# scribe.net
KiCad netlist of a schematic drawn in EasyEDA Pro
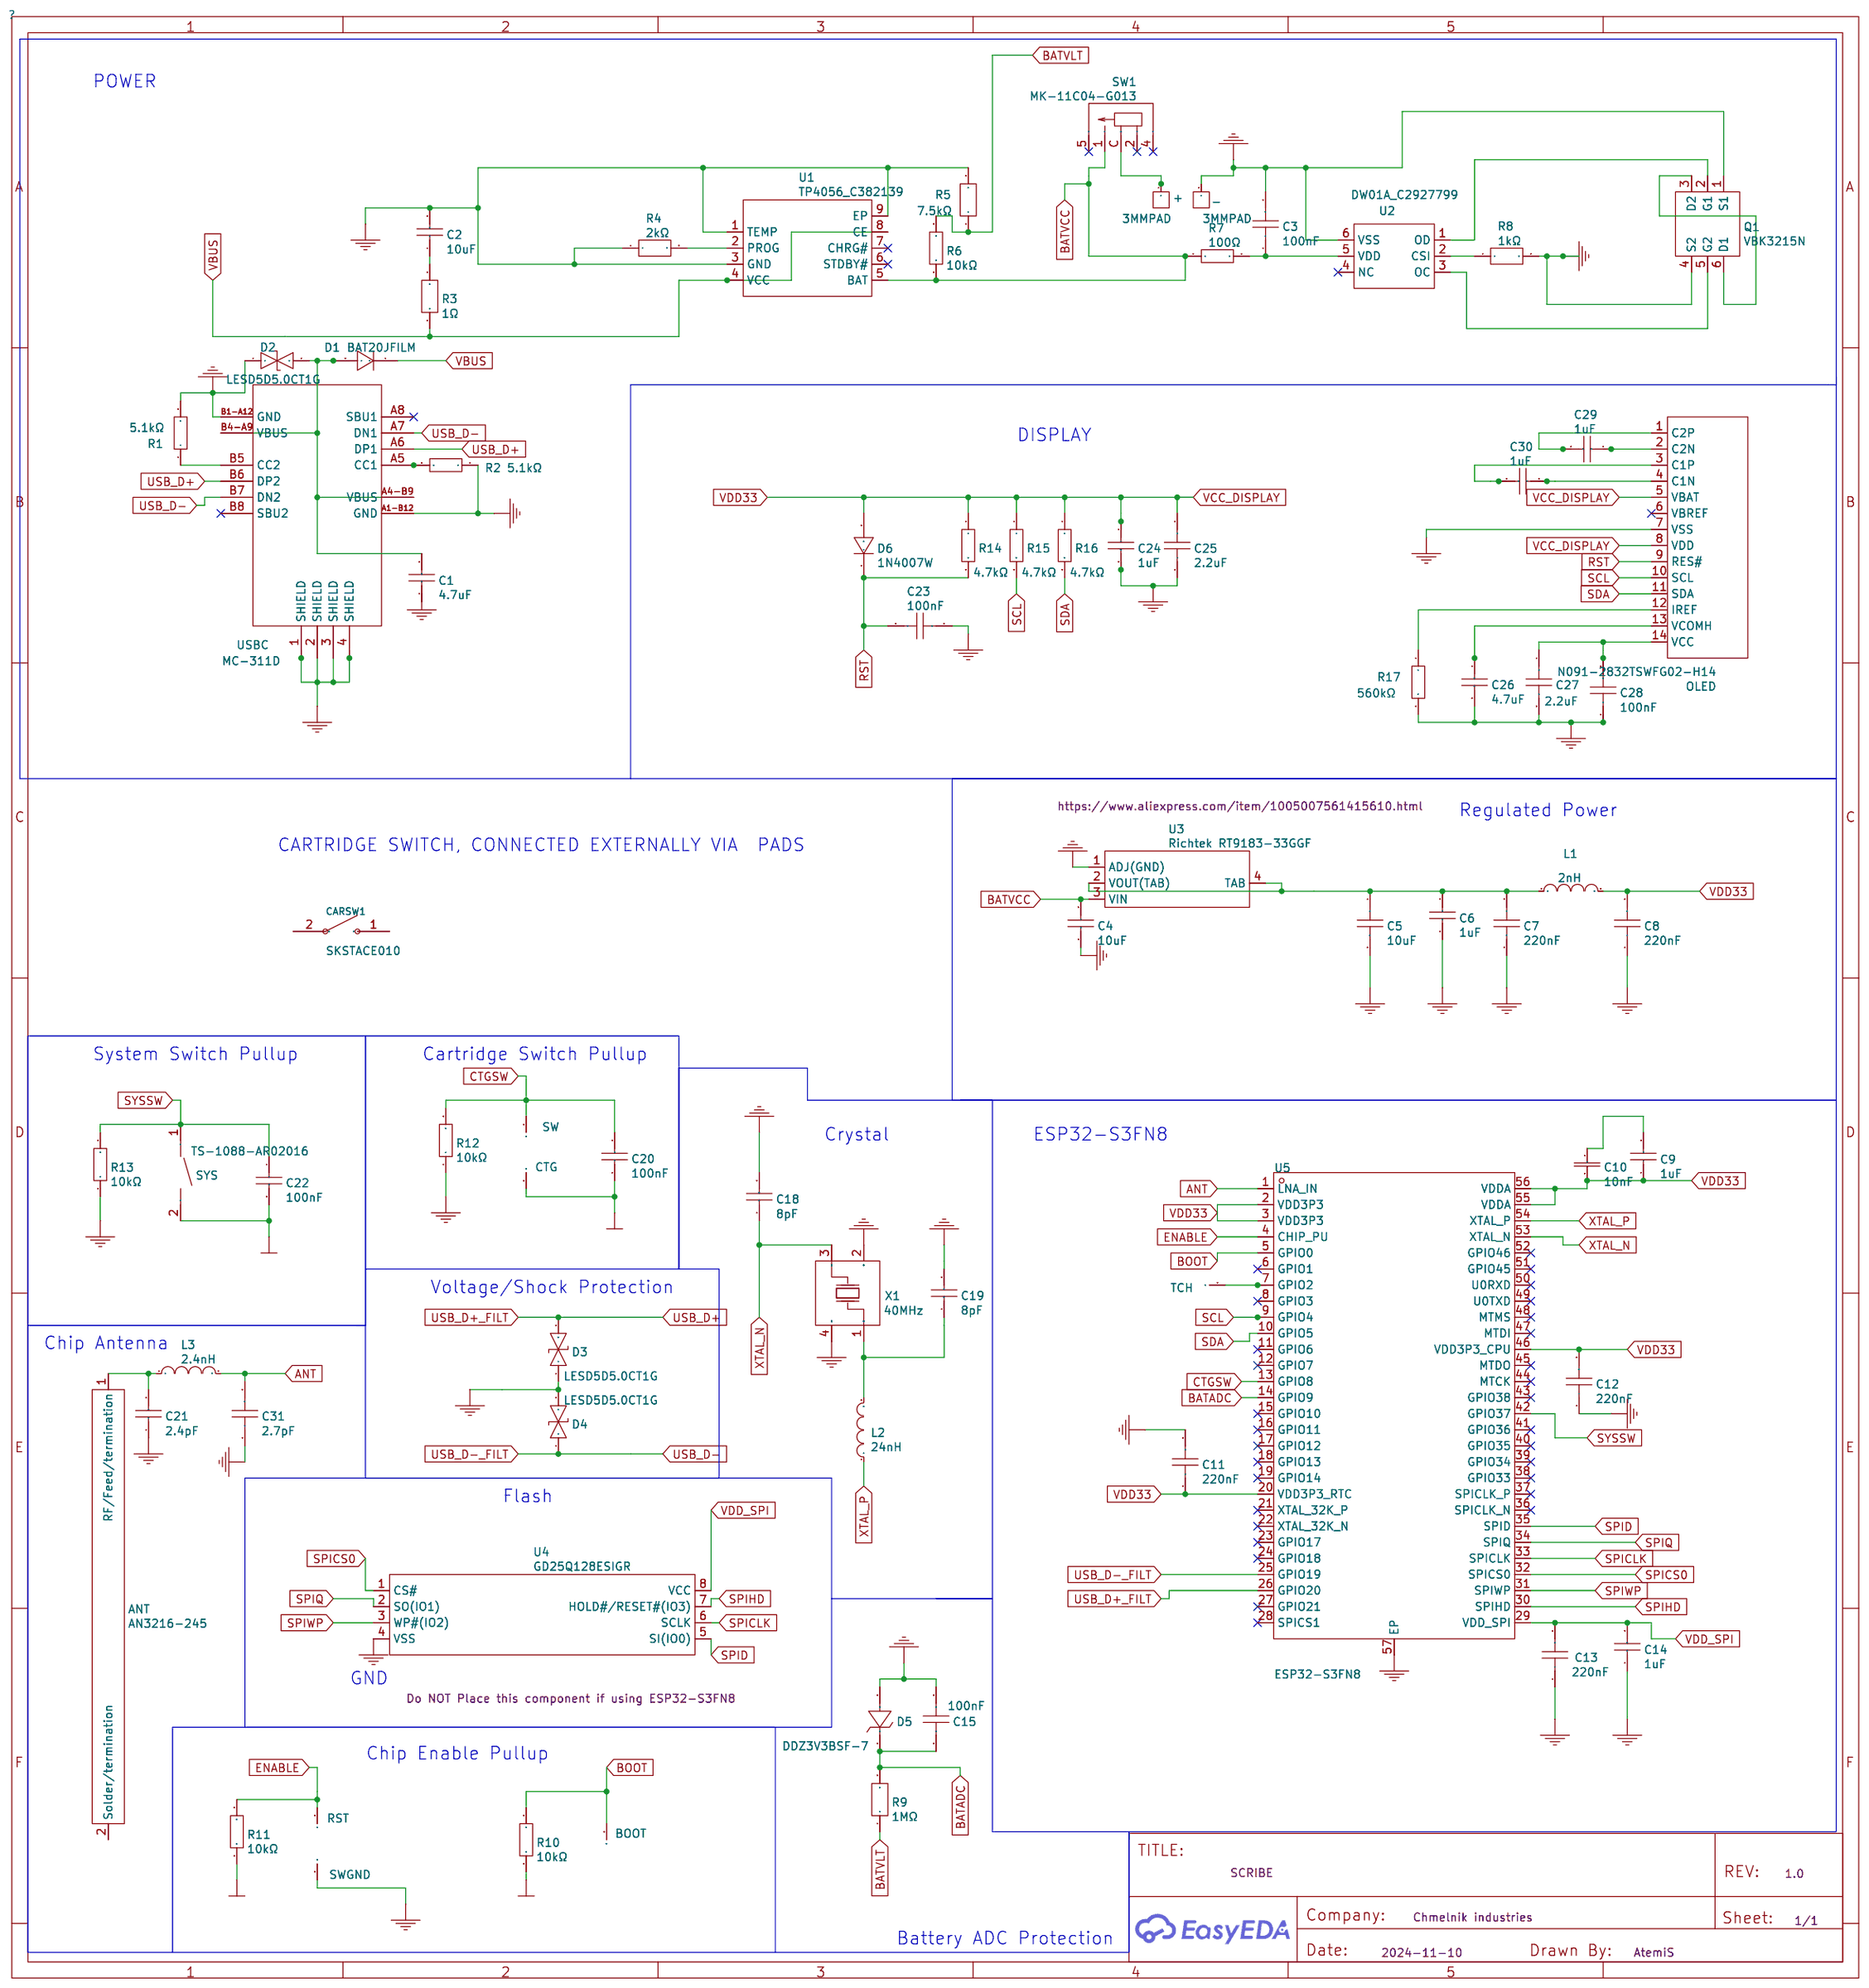
[diagram p0: schematic sheet]

(export (version "E")
  (design (tool "Eeschema 10.0.6"))
  (components
    (comp (ref "+")
      (value "3MMPAD")
      (footprint "easyedapro:3MMPAD")
      (libsource (lib "easyedapro") (part "3MMPAD"))
    )
    (comp (ref "ANT")
      (value "AN3216-245")
      (footprint "easyedapro:ANT-SMD_L3.2-W1.6-A")
      (fields (field (name "Manufacturer") "rainsun(霖昱微)"))
      (libsource (lib "easyedapro") (part "AN3216-245"))
    )
    (comp (ref "BOOT")
      (value "PAD_TERMINAL-32MIL_ROUND")
      (footprint "easyedapro:CON_PAD_ROUND_32MIL")
      (libsource (lib "easyedapro") (part "PAD_TERMINAL-32MIL_ROUND"))
    )
    (comp (ref "C1")
      (value "4.7uF")
      (footprint "easyedapro:C0805")
      (fields
        (field (name "Manufacturer Part") "CL21A475KAQNNNE")
        (field (name "Manufacturer") "SAMSUNG(三星)")
      )
      (libsource (lib "easyedapro") (part "4.7uF"))
    )
    (comp (ref "C2")
      (value "10uF")
      (footprint "easyedapro:C0402")
      (fields
        (field (name "Manufacturer Part") "CL05A106MQ5NUNC")
        (field (name "Manufacturer") "SAMSUNG(三星)")
      )
      (libsource (lib "easyedapro") (part "10uF"))
    )
    (comp (ref "C3")
      (value "100nF")
      (footprint "easyedapro:C0603")
      (fields
        (field (name "Manufacturer Part") "CC0603KRX7R9BB104")
        (field (name "Manufacturer") "YAGEO(国巨)")
      )
      (libsource (lib "easyedapro") (part "100nF"))
    )
    (comp (ref "C4")
      (value "10uF")
      (footprint "easyedapro:C0402")
      (fields
        (field (name "Manufacturer Part") "CL05A106MQ5NUNC")
        (field (name "Manufacturer") "SAMSUNG(三星)")
      )
      (libsource (lib "easyedapro") (part "10uF"))
    )
    (comp (ref "C5")
      (value "10uF")
      (footprint "easyedapro:C0603")
      (fields
        (field (name "Manufacturer Part") "CL10A106KP8NNNC")
        (field (name "Manufacturer") "SAMSUNG(三星)")
      )
      (libsource (lib "") (part "10uF_1"))
    )
    (comp (ref "C6")
      (value "1uF")
      (footprint "easyedapro:C0402")
      (fields
        (field (name "Manufacturer Part") "GRM155R61C105KA12D")
        (field (name "Manufacturer") "muRata(村田)")
      )
      (libsource (lib "easyedapro") (part "1uF"))
    )
    (comp (ref "C7")
      (value "220nF")
      (footprint "easyedapro:C0402")
      (fields
        (field (name "Manufacturer Part") "C0402X7R224K160NT")
        (field (name "Manufacturer") "SANYEAR(叁叶源)")
      )
      (libsource (lib "easyedapro") (part "220nF"))
    )
    (comp (ref "C8")
      (value "220nF")
      (footprint "easyedapro:C0402")
      (fields
        (field (name "Manufacturer Part") "C0402X7R224K160NT")
        (field (name "Manufacturer") "SANYEAR(叁叶源)")
      )
      (libsource (lib "easyedapro") (part "220nF"))
    )
    (comp (ref "C9")
      (value "1uF")
      (footprint "easyedapro:C0402")
      (fields
        (field (name "Manufacturer Part") "GRM155R61C105KA12D")
        (field (name "Manufacturer") "muRata(村田)")
      )
      (libsource (lib "easyedapro") (part "1uF"))
    )
    (comp (ref "C10")
      (value "10nF")
      (footprint "easyedapro:C0201")
      (fields (field (name "Manufacturer Part") "C0603X5R103KDT") (field (name "Manufacturer") "DARFON(达方)"))
      (libsource (lib "easyedapro") (part "10nF"))
    )
    (comp (ref "C11")
      (value "220nF")
      (footprint "easyedapro:C0402")
      (fields
        (field (name "Manufacturer Part") "C0402X7R224K160NT")
        (field (name "Manufacturer") "SANYEAR(叁叶源)")
      )
      (libsource (lib "easyedapro") (part "220nF"))
    )
    (comp (ref "C12")
      (value "220nF")
      (footprint "easyedapro:C0402")
      (fields
        (field (name "Manufacturer Part") "C0402X7R224K160NT")
        (field (name "Manufacturer") "SANYEAR(叁叶源)")
      )
      (libsource (lib "easyedapro") (part "220nF"))
    )
    (comp (ref "C13")
      (value "220nF")
      (footprint "easyedapro:C0402")
      (fields
        (field (name "Manufacturer Part") "C0402X7R224K160NT")
        (field (name "Manufacturer") "SANYEAR(叁叶源)")
      )
      (libsource (lib "easyedapro") (part "220nF"))
    )
    (comp (ref "C14")
      (value "1uF")
      (footprint "easyedapro:C0402")
      (fields
        (field (name "Manufacturer Part") "GRM155R61C105KA12D")
        (field (name "Manufacturer") "muRata(村田)")
      )
      (libsource (lib "easyedapro") (part "1uF"))
    )
    (comp (ref "C15")
      (value "100nF")
      (footprint "easyedapro:C0603")
      (fields
        (field (name "Manufacturer Part") "CC0603KRX7R9BB104")
        (field (name "Manufacturer") "YAGEO(国巨)")
      )
      (libsource (lib "easyedapro") (part "100nF"))
    )
    (comp (ref "C18")
      (value "8pF")
      (footprint "easyedapro:C0402")
      (fields (field (name "Manufacturer Part") "0402CG8R0C500NT") (field (name "Manufacturer") "FH(风华)"))
      (libsource (lib "easyedapro") (part "8pF"))
    )
    (comp (ref "C19")
      (value "8pF")
      (footprint "easyedapro:C0402")
      (fields (field (name "Manufacturer Part") "0402CG8R0C500NT") (field (name "Manufacturer") "FH(风华)"))
      (libsource (lib "easyedapro") (part "8pF"))
    )
    (comp (ref "C20")
      (value "100nF")
      (footprint "easyedapro:C0402")
      (fields
        (field (name "Manufacturer Part") "CL05B104KO5NNNC")
        (field (name "Manufacturer") "SAMSUNG(三星)")
      )
      (libsource (lib "") (part "100nF_1"))
    )
    (comp (ref "C21")
      (value "2.4pF")
      (footprint "easyedapro:C0402")
      (fields (field (name "Manufacturer Part") "0402CG2R4C500NT") (field (name "Manufacturer") "FH(风华)"))
      (libsource (lib "easyedapro") (part "2.4pF"))
    )
    (comp (ref "C22")
      (value "100nF")
      (footprint "easyedapro:C0402")
      (fields
        (field (name "Manufacturer Part") "CL05B104KO5NNNC")
        (field (name "Manufacturer") "SAMSUNG(三星)")
      )
      (libsource (lib "") (part "100nF_1"))
    )
    (comp (ref "C23")
      (value "100nF")
      (footprint "easyedapro:C0603")
      (fields
        (field (name "Manufacturer Part") "CC0603KRX7R9BB104")
        (field (name "Manufacturer") "YAGEO(国巨)")
      )
      (libsource (lib "easyedapro") (part "100nF"))
    )
    (comp (ref "C24")
      (value "1uF")
      (footprint "easyedapro:C0402")
      (fields
        (field (name "Manufacturer Part") "GRM155R61C105KA12D")
        (field (name "Manufacturer") "muRata(村田)")
      )
      (libsource (lib "easyedapro") (part "1uF"))
    )
    (comp (ref "C25")
      (value "2.2uF")
      (footprint "easyedapro:C0603")
      (fields
        (field (name "Manufacturer Part") "C0603C225K8RAC7867")
        (field (name "Manufacturer") "KEMET(基美)")
      )
      (libsource (lib "easyedapro") (part "2.2uF"))
    )
    (comp (ref "C26")
      (value "4.7uF")
      (footprint "easyedapro:C0805")
      (fields
        (field (name "Manufacturer Part") "CL21A475KAQNNNE")
        (field (name "Manufacturer") "SAMSUNG(三星)")
      )
      (libsource (lib "easyedapro") (part "4.7uF"))
    )
    (comp (ref "C27")
      (value "2.2uF")
      (footprint "easyedapro:C0603")
      (fields
        (field (name "Manufacturer Part") "C0603C225K8RAC7867")
        (field (name "Manufacturer") "KEMET(基美)")
      )
      (libsource (lib "easyedapro") (part "2.2uF"))
    )
    (comp (ref "C28")
      (value "100nF")
      (footprint "easyedapro:C0603")
      (fields
        (field (name "Manufacturer Part") "CC0603KRX7R9BB104")
        (field (name "Manufacturer") "YAGEO(国巨)")
      )
      (libsource (lib "easyedapro") (part "100nF"))
    )
    (comp (ref "C29")
      (value "1uF")
      (footprint "easyedapro:C0402")
      (fields
        (field (name "Manufacturer Part") "GRM155R61C105KA12D")
        (field (name "Manufacturer") "muRata(村田)")
      )
      (libsource (lib "easyedapro") (part "1uF"))
    )
    (comp (ref "C30")
      (value "1uF")
      (footprint "easyedapro:C0402")
      (fields
        (field (name "Manufacturer Part") "GRM155R61C105KA12D")
        (field (name "Manufacturer") "muRata(村田)")
      )
      (libsource (lib "easyedapro") (part "1uF"))
    )
    (comp (ref "C31")
      (value "2.7pF")
      (footprint "easyedapro:C0402")
      (fields
        (field (name "Manufacturer Part") "CC0402BRNPO9BN2R7")
        (field (name "Manufacturer") "YAGEO(国巨)")
      )
      (libsource (lib "easyedapro") (part "2.7pF"))
    )
    (comp (ref "CARSW1")
      (value "SKSTACE010")
      (footprint "easyedapro:SW-SMD_L8.5-W8.5-LS8.6")
      (fields (field (name "Manufacturer") "ALPSALPINE(阿尔卑斯阿尔派)"))
      (libsource (lib "easyedapro") (part "SKSTACE010"))
    )
    (comp (ref "CTG")
      (value "PAD_TERMINAL-32MIL_ROUND")
      (footprint "easyedapro:CON_PAD_ROUND_32MIL")
      (libsource (lib "easyedapro") (part "PAD_TERMINAL-32MIL_ROUND"))
    )
    (comp (ref "D1")
      (value "BAT20JFILM")
      (footprint "easyedapro:SOD-323_L1.8-W1.3-LS2.5-RD")
      (fields (field (name "Manufacturer") "ST(意法半导体)"))
      (libsource (lib "easyedapro") (part "BAT20JFILM"))
    )
    (comp (ref "D2")
      (value "LESD5D5.0CT1G")
      (footprint "easyedapro:SOD-523_L1.2-W0.8-LS1.6-BI")
      (fields (field (name "Manufacturer") "LRC(乐山无线电)"))
      (libsource (lib "easyedapro") (part "LESD5D5.0CT1G"))
    )
    (comp (ref "D3")
      (value "LESD5D5.0CT1G")
      (footprint "easyedapro:SOD-523_L1.2-W0.8-LS1.6-BI")
      (fields (field (name "Manufacturer") "LRC(乐山无线电)"))
      (libsource (lib "easyedapro") (part "LESD5D5.0CT1G"))
    )
    (comp (ref "D4")
      (value "LESD5D5.0CT1G")
      (footprint "easyedapro:SOD-523_L1.2-W0.8-LS1.6-BI")
      (fields (field (name "Manufacturer") "LRC(乐山无线电)"))
      (libsource (lib "easyedapro") (part "LESD5D5.0CT1G"))
    )
    (comp (ref "D5")
      (value "DDZ3V3BSF-7")
      (footprint "easyedapro:SOD-323F_L1.7-W1.3-LS2.5-RD")
      (fields (field (name "Manufacturer") "DIODES(美台)"))
      (libsource (lib "easyedapro") (part "DDZ3V3BSF-7"))
    )
    (comp (ref "D6")
      (value "1N4007W")
      (footprint "easyedapro:SOD-123_L2.8-W1.8-LS3.7-RD")
      (fields (field (name "Manufacturer") "BLUE ROCKET"))
      (libsource (lib "easyedapro") (part "1N4007W"))
    )
    (comp (ref "L1")
      (value "2nH")
      (footprint "easyedapro:L0402-RD")
      (fields (field (name "Manufacturer Part") "MLG1005S2N0BTD25") (field (name "Manufacturer") "TDK"))
      (libsource (lib "easyedapro") (part "2nH"))
    )
    (comp (ref "L2")
      (value "24nH")
      (footprint "easyedapro:IND-SMD_L1.2-W0.6")
      (fields
        (field (name "Manufacturer Part") "SDWL1005C24NJSTF")
        (field (name "Manufacturer") "Sunlord(顺络)")
      )
      (libsource (lib "easyedapro") (part "24nH"))
    )
    (comp (ref "L3")
      (value "2.4nH")
      (footprint "easyedapro:L0402")
      (fields (field (name "Manufacturer Part") "LQG15HS2N4S02D") (field (name "Manufacturer") "muRata(村田)"))
      (libsource (lib "easyedapro") (part "2.4nH"))
    )
    (comp (ref "OLED")
      (value "N091-2832TSWFG02-H14")
      (footprint "easyedapro:OLED-SMD_N091-2832TSWFG02-H14")
      (fields (field (name "Manufacturer") "Newvision(新智景)"))
      (libsource (lib "easyedapro") (part "N091-2832TSWFG02-H14"))
    )
    (comp (ref "Q1")
      (value "VBK3215N")
      (footprint "easyedapro:SC-70-6_L2.2-W1.3-P0.65-LS2.1-BR")
      (fields (field (name "Manufacturer") "VBsemi(微碧半导体)"))
      (libsource (lib "easyedapro") (part "VBK3215N"))
    )
    (comp (ref "R1")
      (value "5.1kΩ")
      (footprint "easyedapro:R0603")
      (fields
        (field (name "Manufacturer Part") "0603WAF5101T5E")
        (field (name "Manufacturer") "UNI-ROYAL(厚声)")
      )
      (libsource (lib "easyedapro") (part "5.1kΩ"))
    )
    (comp (ref "R2")
      (value "5.1kΩ")
      (footprint "easyedapro:R0603")
      (fields
        (field (name "Manufacturer Part") "0603WAF5101T5E")
        (field (name "Manufacturer") "UNI-ROYAL(厚声)")
      )
      (libsource (lib "easyedapro") (part "5.1kΩ"))
    )
    (comp (ref "R3")
      (value "1Ω")
      (footprint "easyedapro:R1206")
      (fields (field (name "Manufacturer Part") "RT1206BRD071RL") (field (name "Manufacturer") "YAGEO(国巨)"))
      (libsource (lib "easyedapro") (part "1Ω"))
    )
    (comp (ref "R4")
      (value "2kΩ")
      (footprint "easyedapro:RES-SMD_L3.5-W1.5")
      (fields
        (field (name "Manufacturer Part") "RJM74P0204F2T2001")
        (field (name "Manufacturer") "Tyohm(幸亚电阻)")
      )
      (libsource (lib "easyedapro") (part "2kΩ"))
    )
    (comp (ref "R5")
      (value "7.5kΩ")
      (footprint "easyedapro:R1206")
      (fields (field (name "Manufacturer Part") "RT1206BRD077K5L") (field (name "Manufacturer") "YAGEO(国巨)"))
      (libsource (lib "easyedapro") (part "7.5kΩ"))
    )
    (comp (ref "R6")
      (value "10kΩ")
      (footprint "easyedapro:R1206")
      (fields (field (name "Manufacturer Part") "RT1206BRD0710KL") (field (name "Manufacturer") "YAGEO(国巨)"))
      (libsource (lib "") (part "10kΩ_1"))
    )
    (comp (ref "R7")
      (value "100Ω")
      (footprint "easyedapro:R1206")
      (fields (field (name "Manufacturer Part") "RT1206BRD07100RL") (field (name "Manufacturer") "YAGEO(国巨)"))
      (libsource (lib "easyedapro") (part "100Ω"))
    )
    (comp (ref "R8")
      (value "1kΩ")
      (footprint "easyedapro:R1206")
      (fields (field (name "Manufacturer Part") "RT1206BRD071KL") (field (name "Manufacturer") "YAGEO(国巨)"))
      (libsource (lib "easyedapro") (part "1kΩ"))
    )
    (comp (ref "R9")
      (value "1MΩ")
      (footprint "easyedapro:R0603")
      (fields (field (name "Manufacturer Part") "ERJP03J105V") (field (name "Manufacturer") "PANASONIC(松下)"))
      (libsource (lib "easyedapro") (part "1MΩ"))
    )
    (comp (ref "R10")
      (value "10kΩ")
      (footprint "easyedapro:R0603")
      (fields
        (field (name "Manufacturer Part") "0603WAF1002T5E")
        (field (name "Manufacturer") "UNI-ROYAL(厚声)")
      )
      (libsource (lib "easyedapro") (part "10kΩ"))
    )
    (comp (ref "R11")
      (value "10kΩ")
      (footprint "easyedapro:R0603")
      (fields
        (field (name "Manufacturer Part") "0603WAF1002T5E")
        (field (name "Manufacturer") "UNI-ROYAL(厚声)")
      )
      (libsource (lib "easyedapro") (part "10kΩ"))
    )
    (comp (ref "R12")
      (value "10kΩ")
      (footprint "easyedapro:R0603")
      (fields
        (field (name "Manufacturer Part") "0603WAF1002T5E")
        (field (name "Manufacturer") "UNI-ROYAL(厚声)")
      )
      (libsource (lib "easyedapro") (part "10kΩ"))
    )
    (comp (ref "R13")
      (value "10kΩ")
      (footprint "easyedapro:R0603")
      (fields
        (field (name "Manufacturer Part") "0603WAF1002T5E")
        (field (name "Manufacturer") "UNI-ROYAL(厚声)")
      )
      (libsource (lib "easyedapro") (part "10kΩ"))
    )
    (comp (ref "R14")
      (value "4.7kΩ")
      (footprint "easyedapro:R0603")
      (fields (field (name "Manufacturer Part") "ARG03BTC4701") (field (name "Manufacturer") "Viking(光颉)"))
      (libsource (lib "easyedapro") (part "4.7kΩ"))
    )
    (comp (ref "R15")
      (value "4.7kΩ")
      (footprint "easyedapro:R0603")
      (fields (field (name "Manufacturer Part") "ARG03BTC4701") (field (name "Manufacturer") "Viking(光颉)"))
      (libsource (lib "easyedapro") (part "4.7kΩ"))
    )
    (comp (ref "R16")
      (value "4.7kΩ")
      (footprint "easyedapro:R0603")
      (fields (field (name "Manufacturer Part") "ARG03BTC4701") (field (name "Manufacturer") "Viking(光颉)"))
      (libsource (lib "easyedapro") (part "4.7kΩ"))
    )
    (comp (ref "R17")
      (value "560kΩ")
      (footprint "easyedapro:R1206")
      (fields (field (name "Manufacturer Part") "RC1206FR-07560KL") (field (name "Manufacturer") "YAGEO(国巨)"))
      (libsource (lib "easyedapro") (part "560kΩ"))
    )
    (comp (ref "RST")
      (value "PAD_TERMINAL-32MIL_ROUND")
      (footprint "easyedapro:CON_PAD_ROUND_32MIL")
      (libsource (lib "easyedapro") (part "PAD_TERMINAL-32MIL_ROUND"))
    )
    (comp (ref "SW")
      (value "PAD_TERMINAL-32MIL_ROUND")
      (footprint "easyedapro:CON_PAD_ROUND_32MIL")
      (libsource (lib "easyedapro") (part "PAD_TERMINAL-32MIL_ROUND"))
    )
    (comp (ref "SW1")
      (value "MK-11C04-G013")
      (footprint "easyedapro:SW-SMD_MK-11C04-G013")
      (fields (field (name "Manufacturer") "G-Switch(品赞)"))
      (libsource (lib "easyedapro") (part "MK-11C04-G013"))
    )
    (comp (ref "SWGND")
      (value "PAD_TERMINAL-32MIL_ROUND")
      (footprint "easyedapro:CON_PAD_ROUND_32MIL")
      (libsource (lib "easyedapro") (part "PAD_TERMINAL-32MIL_ROUND"))
    )
    (comp (ref "SYS")
      (value "TS-1088-AR02016")
      (footprint "easyedapro:SW-SMD_L3.9-W3.0-P4.45")
      (fields (field (name "Manufacturer") "XUNPU(讯普)"))
      (libsource (lib "easyedapro") (part "TS-1088-AR02016"))
    )
    (comp (ref "TCH")
      (value "PAD_TERMINAL-32MIL_ROUND")
      (footprint "easyedapro:CON_PAD_ROUND_32MIL")
      (libsource (lib "easyedapro") (part "PAD_TERMINAL-32MIL_ROUND"))
    )
    (comp (ref "U1")
      (value "TP4056_C382139")
      (footprint "easyedapro:ESOP-8_L4.9-W3.9-P1.27-LS6.0-BL-EP")
      (fields (field (name "Manufacturer Part") "TP4056") (field (name "Manufacturer") "TPOWER(天源)"))
      (libsource (lib "easyedapro") (part "TP4056_C382139"))
    )
    (comp (ref "U2")
      (value "DW01A_C2927799")
      (footprint "easyedapro:SOT-23-6_L2.9-W1.6-P0.95-LS2.8-BL")
      (fields (field (name "Manufacturer Part") "DW01A") (field (name "Manufacturer") "YONGYUTAI(永裕泰)"))
      (libsource (lib "easyedapro") (part "DW01A_C2927799"))
    )
    (comp (ref "U3")
      (value "Richtek RT9183-33GGF")
      (footprint "easyedapro:SOT-223-4_L6.5-W3.5-P2.30-LS7.0-BR")
      (description "You need to source this yoursef. LCSC doesnt have it")
      (fields
        (field (name "Manufacturer Part") "RT9183-33GGF")
        (field (name "Manufacturer") "Richtek")
        (field (name "Link") "https://www.aliexpress.com/item/1005007561415610.html")
      )
      (libsource (lib "easyedapro") (part "AMS1117-3.3_C347222"))
    )
    (comp (ref "U4")
      (value "GD25Q128ESIGR")
      (footprint "easyedapro:SOP-8_L5.3-W5.3-P1.27-LS8.0-BL")
      (description "Do NOT Place this component if using ESP32-S3FN8")
      (fields (field (name "Manufacturer") "GigaDevice(兆易创新)"))
      (libsource (lib "easyedapro") (part "GD25Q128ESIGR"))
    )
    (comp (ref "U5")
      (value "ESP32-S3FN8")
      (footprint "easyedapro:QFN-56_L7.0-W7.0-P0.40-TL-EP4.0")
      (fields (field (name "Manufacturer") "ESPRESSIF(乐鑫)"))
      (libsource (lib "easyedapro") (part "ESP32-S3(FN8)"))
    )
    (comp (ref "USBC")
      (value "MC-311D")
      (footprint "easyedapro:USB-C-SMD_MC-311D")
      (fields (field (name "Manufacturer") "SOFNG(硕方)"))
      (libsource (lib "easyedapro") (part "MC-311D"))
    )
    (comp (ref "X1")
      (value "40MHz")
      (footprint "easyedapro:CRYSTAL-SMD_4P-L2.5-W2.0-BL")
      (fields (field (name "Manufacturer Part") "K2C400000910") (field (name "Manufacturer") "KYX(凯越翔)"))
      (libsource (lib "easyedapro") (part "40MHz"))
    )
    (comp (ref "_")
      (value "3MMPAD")
      (footprint "easyedapro:3MMPAD")
      (libsource (lib "easyedapro") (part "3MMPAD"))
    )
  )
  (nets
    (net (code "1") (name "ANT") (class "Default")
      (node (ref "C31") (pin "2") (pinfunction "2_2") (pintype "unspecified"))
      (node (ref "L3") (pin "2") (pinfunction "2_2") (pintype "unspecified"))
      (node (ref "U5") (pin "1") (pinfunction "LNA_IN_1") (pintype "unspecified"))
    )
    (net (code "2") (name "BATADC") (class "Default")
      (node (ref "C15") (pin "1") (pinfunction "1_1") (pintype "unspecified"))
      (node (ref "D5") (pin "1") (pinfunction "K_1") (pintype "unspecified"))
      (node (ref "R9") (pin "2") (pinfunction "2_2") (pintype "unspecified"))
      (node (ref "U5") (pin "14") (pinfunction "GPIO9_14") (pintype "unspecified"))
    )
    (net (code "3") (name "BATVCC") (class "Default")
      (node (ref "C4") (pin "2") (pinfunction "2_2") (pintype "input"))
      (node (ref "R6") (pin "1") (pinfunction "1_1") (pintype "unspecified"))
      (node (ref "R7") (pin "1") (pinfunction "1_1") (pintype "unspecified"))
      (node (ref "SW1") (pin "1") (pinfunction "1_1") (pintype "unspecified"))
      (node (ref "U1") (pin "5") (pinfunction "BAT_5") (pintype "unspecified"))
      (node (ref "U3") (pin "3") (pinfunction "VIN_3") (pintype "unspecified"))
    )
    (net (code "4") (name "BATVLT") (class "Default")
      (node (ref "R5") (pin "1") (pinfunction "1_1") (pintype "unspecified"))
      (node (ref "R6") (pin "2") (pinfunction "2_2") (pintype "unspecified"))
      (node (ref "R9") (pin "1") (pinfunction "1_1") (pintype "unspecified"))
    )
    (net (code "5") (name "BOOT") (class "Default")
      (node (ref "BOOT") (pin "P") (pinfunction "P_P") (pintype "unspecified"))
      (node (ref "R10") (pin "2") (pinfunction "2_2") (pintype "input"))
      (node (ref "U5") (pin "5") (pinfunction "GPIO0_5") (pintype "unspecified"))
    )
    (net (code "6") (name "CTGSW") (class "Default")
      (node (ref "C20") (pin "1") (pinfunction "1_1") (pintype "input"))
      (node (ref "R12") (pin "2") (pinfunction "2_2") (pintype "input"))
      (node (ref "SW") (pin "P") (pinfunction "P_P") (pintype "unspecified"))
      (node (ref "U5") (pin "13") (pinfunction "GPIO8_13") (pintype "unspecified"))
    )
    (net (code "7") (name "ENABLE") (class "Default")
      (node (ref "R11") (pin "2") (pinfunction "2_2") (pintype "input"))
      (node (ref "RST") (pin "P") (pinfunction "P_P") (pintype "unspecified"))
      (node (ref "U5") (pin "4") (pinfunction "CHIP_PU_4") (pintype "unspecified"))
    )
    (net (code "8") (name "GND") (class "Default")
      (node (ref "C1") (pin "1") (pinfunction "1_1") (pintype "input"))
      (node (ref "C11") (pin "2") (pinfunction "2_2") (pintype "unspecified"))
      (node (ref "C12") (pin "1") (pinfunction "1_1") (pintype "unspecified"))
      (node (ref "C13") (pin "1") (pinfunction "1_1") (pintype "unspecified"))
      (node (ref "C14") (pin "1") (pinfunction "1_1") (pintype "input"))
      (node (ref "C15") (pin "2") (pinfunction "2_2") (pintype "unspecified"))
      (node (ref "C18") (pin "2") (pinfunction "2_2") (pintype "input"))
      (node (ref "C19") (pin "2") (pinfunction "2_2") (pintype "input"))
      (node (ref "C2") (pin "2") (pinfunction "2_2") (pintype "input"))
      (node (ref "C21") (pin "1") (pinfunction "1_1") (pintype "input"))
      (node (ref "C23") (pin "1") (pinfunction "1_1") (pintype "unspecified"))
      (node (ref "C24") (pin "2") (pinfunction "2_2") (pintype "input"))
      (node (ref "C25") (pin "2") (pinfunction "2_2") (pintype "unspecified"))
      (node (ref "C26") (pin "2") (pinfunction "2_2") (pintype "input"))
      (node (ref "C27") (pin "2") (pinfunction "2_2") (pintype "unspecified"))
      (node (ref "C28") (pin "1") (pinfunction "1_1") (pintype "unspecified"))
      (node (ref "C3") (pin "2") (pinfunction "2_2") (pintype "unspecified"))
      (node (ref "C31") (pin "1") (pinfunction "1_1") (pintype "unspecified"))
      (node (ref "C4") (pin "1") (pinfunction "1_1") (pintype "input"))
      (node (ref "C5") (pin "2") (pinfunction "2_2") (pintype "unspecified"))
      (node (ref "C6") (pin "1") (pinfunction "1_1") (pintype "input"))
      (node (ref "C7") (pin "1") (pinfunction "1_1") (pintype "unspecified"))
      (node (ref "C8") (pin "1") (pinfunction "1_1") (pintype "unspecified"))
      (node (ref "D2") (pin "1") (pinfunction "1_1") (pintype "unspecified"))
      (node (ref "D3") (pin "1") (pinfunction "1_1") (pintype "unspecified"))
      (node (ref "D4") (pin "2") (pinfunction "2_2") (pintype "unspecified"))
      (node (ref "D5") (pin "2") (pinfunction "A_2") (pintype "unspecified"))
      (node (ref "OLED") (pin "7") (pinfunction "VSS_7") (pintype "unspecified"))
      (node (ref "Q1") (pin "1") (pinfunction "S1_1") (pintype "unspecified"))
      (node (ref "Q1") (pin "4") (pinfunction "S2_4") (pintype "unspecified"))
      (node (ref "R1") (pin "2") (pinfunction "2_2") (pintype "input"))
      (node (ref "R12") (pin "1") (pinfunction "1_1") (pintype "input"))
      (node (ref "R13") (pin "1") (pinfunction "1_1") (pintype "input"))
      (node (ref "R17") (pin "2") (pinfunction "2_2") (pintype "input"))
      (node (ref "R2") (pin "1") (pinfunction "1_1") (pintype "input"))
      (node (ref "R4") (pin "1") (pinfunction "1_1") (pintype "unspecified"))
      (node (ref "R5") (pin "2") (pinfunction "2_2") (pintype "unspecified"))
      (node (ref "R8") (pin "2") (pinfunction "2_2") (pintype "unspecified"))
      (node (ref "SWGND") (pin "P") (pinfunction "P_P") (pintype "unspecified"))
      (node (ref "U1") (pin "1") (pinfunction "TEMP_1") (pintype "unspecified"))
      (node (ref "U1") (pin "3") (pinfunction "GND_3") (pintype "unspecified"))
      (node (ref "U1") (pin "9") (pinfunction "EP_9") (pintype "unspecified"))
      (node (ref "U2") (pin "6") (pinfunction "VSS_6") (pintype "unspecified"))
      (node (ref "U3") (pin "1") (pinfunction "ADJ(GND)_1") (pintype "unspecified"))
      (node (ref "U4") (pin "4") (pinfunction "VSS_4") (pintype "unspecified"))
      (node (ref "U5") (pin "57") (pinfunction "EP_57") (pintype "unspecified"))
      (node (ref "USBC") (pin "1") (pinfunction "SHIELD_1") (pintype "unspecified"))
      (node (ref "USBC") (pin "2") (pinfunction "SHIELD_2") (pintype "unspecified"))
      (node (ref "USBC") (pin "3") (pinfunction "SHIELD_3") (pintype "unspecified"))
      (node (ref "USBC") (pin "4") (pinfunction "SHIELD_4") (pintype "unspecified"))
      (node (ref "USBC") (pin "A1-B12") (pinfunction "GND_A1-B12") (pintype "unspecified"))
      (node (ref "USBC") (pin "B1-A12") (pinfunction "GND_B1-A12") (pintype "unspecified"))
      (node (ref "X1") (pin "2") (pinfunction "GND_2") (pintype "unspecified"))
      (node (ref "X1") (pin "4") (pinfunction "GND_4") (pintype "unspecified"))
      (node (ref "_") (pin "1") (pinfunction "1_1") (pintype "unspecified"))
    )
    (net (code "9") (name "Net-(+-Pad1)") (class "Default")
      (node (ref "+") (pin "1") (pinfunction "1_1") (pintype "unspecified"))
      (node (ref "SW1") (pin "C") (pinfunction "C_C") (pintype "unspecified"))
    )
    (net (code "10") (name "Net-(ANT-RF{slash}Feed{slash}termination)") (class "Default")
      (node (ref "ANT") (pin "1") (pinfunction "RF/Feed/termination_1") (pintype "unspecified"))
      (node (ref "C21") (pin "2") (pinfunction "2_2") (pintype "input"))
      (node (ref "L3") (pin "1") (pinfunction "1_1") (pintype "unspecified"))
    )
    (net (code "11") (name "Net-(C2-Pad1)") (class "Default")
      (node (ref "C2") (pin "1") (pinfunction "1_1") (pintype "input"))
      (node (ref "R3") (pin "1") (pinfunction "1_1") (pintype "unspecified"))
    )
    (net (code "12") (name "Net-(C10-Pad1)") (class "Default")
      (node (ref "C10") (pin "1") (pinfunction "1_1") (pintype "input"))
      (node (ref "C9") (pin "2") (pinfunction "2_2") (pintype "input"))
    )
    (net (code "13") (name "Net-(D1-A)") (class "Default")
      (node (ref "C1") (pin "2") (pinfunction "2_2") (pintype "input"))
      (node (ref "D1") (pin "2") (pinfunction "A_2") (pintype "unspecified"))
      (node (ref "D2") (pin "2") (pinfunction "2_2") (pintype "unspecified"))
      (node (ref "USBC") (pin "A4-B9") (pinfunction "VBUS_A4-B9") (pintype "unspecified"))
      (node (ref "USBC") (pin "B4-A9") (pinfunction "VBUS_B4-A9") (pintype "unspecified"))
    )
    (net (code "14") (name "Net-(OLED-C1N)") (class "Default")
      (node (ref "C30") (pin "1") (pinfunction "1_1") (pintype "input"))
      (node (ref "OLED") (pin "4") (pinfunction "C1N_4") (pintype "unspecified"))
    )
    (net (code "15") (name "Net-(OLED-C1P)") (class "Default")
      (node (ref "C30") (pin "2") (pinfunction "2_2") (pintype "input"))
      (node (ref "OLED") (pin "3") (pinfunction "C1P_3") (pintype "unspecified"))
    )
    (net (code "16") (name "Net-(OLED-C2N)") (class "Default")
      (node (ref "C29") (pin "1") (pinfunction "1_1") (pintype "input"))
      (node (ref "OLED") (pin "2") (pinfunction "C2N_2") (pintype "unspecified"))
    )
    (net (code "17") (name "Net-(OLED-C2P)") (class "Default")
      (node (ref "C29") (pin "2") (pinfunction "2_2") (pintype "input"))
      (node (ref "OLED") (pin "1") (pinfunction "C2P_1") (pintype "unspecified"))
    )
    (net (code "18") (name "Net-(OLED-IREF)") (class "Default")
      (node (ref "OLED") (pin "12") (pinfunction "IREF_12") (pintype "unspecified"))
      (node (ref "R17") (pin "1") (pinfunction "1_1") (pintype "input"))
    )
    (net (code "19") (name "Net-(OLED-VCC)") (class "Default")
      (node (ref "C27") (pin "1") (pinfunction "1_1") (pintype "unspecified"))
      (node (ref "C28") (pin "2") (pinfunction "2_2") (pintype "unspecified"))
      (node (ref "OLED") (pin "14") (pinfunction "VCC_14") (pintype "unspecified"))
    )
    (net (code "20") (name "Net-(OLED-VCOMH)") (class "Default")
      (node (ref "C26") (pin "1") (pinfunction "1_1") (pintype "input"))
      (node (ref "OLED") (pin "13") (pinfunction "VCOMH_13") (pintype "unspecified"))
    )
    (net (code "21") (name "Net-(Q1-D1)") (class "Default")
      (node (ref "Q1") (pin "3") (pinfunction "D2_3") (pintype "unspecified"))
      (node (ref "Q1") (pin "6") (pinfunction "D1_6") (pintype "unspecified"))
    )
    (net (code "22") (name "Net-(Q1-G1)") (class "Default")
      (node (ref "Q1") (pin "2") (pinfunction "G1_2") (pintype "unspecified"))
      (node (ref "U2") (pin "1") (pinfunction "OD_1") (pintype "unspecified"))
    )
    (net (code "23") (name "Net-(Q1-G2)") (class "Default")
      (node (ref "Q1") (pin "5") (pinfunction "G2_5") (pintype "unspecified"))
      (node (ref "U2") (pin "3") (pinfunction "OC_3") (pintype "unspecified"))
    )
    (net (code "24") (name "Net-(U1-PROG)") (class "Default")
      (node (ref "R4") (pin "2") (pinfunction "2_2") (pintype "unspecified"))
      (node (ref "U1") (pin "2") (pinfunction "PROG_2") (pintype "unspecified"))
    )
    (net (code "25") (name "Net-(U2-CSI)") (class "Default")
      (node (ref "R8") (pin "1") (pinfunction "1_1") (pintype "unspecified"))
      (node (ref "U2") (pin "2") (pinfunction "CSI_2") (pintype "unspecified"))
    )
    (net (code "26") (name "Net-(U2-VDD)") (class "Default")
      (node (ref "C3") (pin "1") (pinfunction "1_1") (pintype "unspecified"))
      (node (ref "R7") (pin "2") (pinfunction "2_2") (pintype "unspecified"))
      (node (ref "U2") (pin "5") (pinfunction "VDD_5") (pintype "unspecified"))
    )
    (net (code "27") (name "Net-(U3-TAB)") (class "Default")
      (node (ref "C5") (pin "1") (pinfunction "1_1") (pintype "unspecified"))
      (node (ref "C6") (pin "2") (pinfunction "2_2") (pintype "input"))
      (node (ref "C7") (pin "2") (pinfunction "2_2") (pintype "unspecified"))
      (node (ref "L1") (pin "1") (pinfunction "1_1") (pintype "unspecified"))
      (node (ref "U3") (pin "2") (pinfunction "VOUT(TAB)_2") (pintype "unspecified"))
      (node (ref "U3") (pin "4") (pinfunction "TAB_4") (pintype "unspecified"))
    )
    (net (code "28") (name "Net-(U5-GPIO2)") (class "Default")
      (node (ref "TCH") (pin "P") (pinfunction "P_P") (pintype "unspecified"))
      (node (ref "U5") (pin "7") (pinfunction "GPIO2_7") (pintype "unspecified"))
    )
    (net (code "29") (name "Net-(USBC-CC1)") (class "Default")
      (node (ref "R2") (pin "2") (pinfunction "2_2") (pintype "input"))
      (node (ref "USBC") (pin "A5") (pinfunction "CC1_A5") (pintype "unspecified"))
    )
    (net (code "30") (name "Net-(USBC-CC2)") (class "Default")
      (node (ref "R1") (pin "1") (pinfunction "1_1") (pintype "input"))
      (node (ref "USBC") (pin "B5") (pinfunction "CC2_B5") (pintype "unspecified"))
    )
    (net (code "31") (name "Net-(X1-OSC1)") (class "Default")
      (node (ref "C19") (pin "1") (pinfunction "1_1") (pintype "input"))
      (node (ref "L2") (pin "2") (pinfunction "2_2") (pintype "unspecified"))
      (node (ref "X1") (pin "1") (pinfunction "OSC1_1") (pintype "unspecified"))
    )
    (net (code "32") (name "RST") (class "Default")
      (node (ref "C23") (pin "2") (pinfunction "2_2") (pintype "unspecified"))
      (node (ref "D6") (pin "1") (pinfunction "1_1") (pintype "unspecified"))
      (node (ref "OLED") (pin "9") (pinfunction "RES#_9") (pintype "unspecified"))
      (node (ref "R14") (pin "2") (pinfunction "2_2") (pintype "unspecified"))
    )
    (net (code "33") (name "SCL") (class "Default")
      (node (ref "OLED") (pin "10") (pinfunction "SCL_10") (pintype "unspecified"))
      (node (ref "R15") (pin "2") (pinfunction "2_2") (pintype "unspecified"))
      (node (ref "U5") (pin "9") (pinfunction "GPIO4_9") (pintype "unspecified"))
    )
    (net (code "34") (name "SDA") (class "Default")
      (node (ref "OLED") (pin "11") (pinfunction "SDA_11") (pintype "unspecified"))
      (node (ref "R16") (pin "2") (pinfunction "2_2") (pintype "unspecified"))
      (node (ref "U5") (pin "10") (pinfunction "GPIO5_10") (pintype "unspecified"))
    )
    (net (code "35") (name "SPICLK") (class "Default")
      (node (ref "U4") (pin "6") (pinfunction "SCLK_6") (pintype "unspecified"))
      (node (ref "U5") (pin "33") (pinfunction "SPICLK_33") (pintype "unspecified"))
    )
    (net (code "36") (name "SPICS0") (class "Default")
      (node (ref "U4") (pin "1") (pinfunction "CS#_1") (pintype "unspecified"))
      (node (ref "U5") (pin "32") (pinfunction "SPICS0_32") (pintype "unspecified"))
    )
    (net (code "37") (name "SPID") (class "Default")
      (node (ref "U4") (pin "5") (pinfunction "SI(IO0)_5") (pintype "unspecified"))
      (node (ref "U5") (pin "35") (pinfunction "SPID_35") (pintype "unspecified"))
    )
    (net (code "38") (name "SPIHD") (class "Default")
      (node (ref "U4") (pin "7") (pinfunction "HOLD#/RESET#(IO3)_7") (pintype "unspecified"))
      (node (ref "U5") (pin "30") (pinfunction "SPIHD_30") (pintype "unspecified"))
    )
    (net (code "39") (name "SPIQ") (class "Default")
      (node (ref "U4") (pin "2") (pinfunction "SO(IO1)_2") (pintype "unspecified"))
      (node (ref "U5") (pin "34") (pinfunction "SPIQ_34") (pintype "unspecified"))
    )
    (net (code "40") (name "SPIWP") (class "Default")
      (node (ref "U4") (pin "3") (pinfunction "WP#(IO2)_3") (pintype "unspecified"))
      (node (ref "U5") (pin "31") (pinfunction "SPIWP_31") (pintype "unspecified"))
    )
    (net (code "41") (name "SYSSW") (class "Default")
      (node (ref "C22") (pin "1") (pinfunction "1_1") (pintype "input"))
      (node (ref "R13") (pin "2") (pinfunction "2_2") (pintype "input"))
      (node (ref "SYS") (pin "1") (pinfunction "1_1") (pintype "unspecified"))
      (node (ref "U5") (pin "42") (pinfunction "GPIO37_42") (pintype "unspecified"))
    )
    (net (code "42") (name "USB_D+") (class "Default")
      (node (ref "D3") (pin "2") (pinfunction "2_2") (pintype "unspecified"))
      (node (ref "U5") (pin "26") (pinfunction "GPIO20_26") (pintype "unspecified"))
      (node (ref "USBC") (pin "A6") (pinfunction "DP1_A6") (pintype "unspecified"))
      (node (ref "USBC") (pin "B6") (pinfunction "DP2_B6") (pintype "unspecified"))
    )
    (net (code "43") (name "USB_D-") (class "Default")
      (node (ref "D4") (pin "1") (pinfunction "1_1") (pintype "unspecified"))
      (node (ref "U5") (pin "25") (pinfunction "GPIO19_25") (pintype "unspecified"))
      (node (ref "USBC") (pin "A7") (pinfunction "DN1_A7") (pintype "unspecified"))
      (node (ref "USBC") (pin "B7") (pinfunction "DN2_B7") (pintype "unspecified"))
    )
    (net (code "44") (name "VBUS") (class "Default")
      (node (ref "D1") (pin "1") (pinfunction "K_1") (pintype "unspecified"))
      (node (ref "R3") (pin "2") (pinfunction "2_2") (pintype "unspecified"))
      (node (ref "U1") (pin "4") (pinfunction "VCC_4") (pintype "unspecified"))
      (node (ref "U1") (pin "8") (pinfunction "CE_8") (pintype "unspecified"))
    )
    (net (code "45") (name "VCC_DISPLAY") (class "Default")
      (node (ref "C10") (pin "2") (pinfunction "2_2") (pintype "input"))
      (node (ref "C11") (pin "1") (pinfunction "1_1") (pintype "unspecified"))
      (node (ref "C12") (pin "2") (pinfunction "2_2") (pintype "unspecified"))
      (node (ref "C20") (pin "2") (pinfunction "2_2") (pintype "input"))
      (node (ref "C22") (pin "2") (pinfunction "2_2") (pintype "input"))
      (node (ref "C24") (pin "1") (pinfunction "1_1") (pintype "input"))
      (node (ref "C25") (pin "1") (pinfunction "1_1") (pintype "unspecified"))
      (node (ref "C8") (pin "2") (pinfunction "2_2") (pintype "unspecified"))
      (node (ref "C9") (pin "1") (pinfunction "1_1") (pintype "input"))
      (node (ref "CTG") (pin "P") (pinfunction "P_P") (pintype "unspecified"))
      (node (ref "D6") (pin "2") (pinfunction "2_2") (pintype "unspecified"))
      (node (ref "L1") (pin "2") (pinfunction "2_2") (pintype "unspecified"))
      (node (ref "OLED") (pin "5") (pinfunction "VBAT_5") (pintype "unspecified"))
      (node (ref "OLED") (pin "8") (pinfunction "VDD_8") (pintype "unspecified"))
      (node (ref "R10") (pin "1") (pinfunction "1_1") (pintype "input"))
      (node (ref "R11") (pin "1") (pinfunction "1_1") (pintype "input"))
      (node (ref "R14") (pin "1") (pinfunction "1_1") (pintype "unspecified"))
      (node (ref "R15") (pin "1") (pinfunction "1_1") (pintype "unspecified"))
      (node (ref "R16") (pin "1") (pinfunction "1_1") (pintype "unspecified"))
      (node (ref "SYS") (pin "2") (pinfunction "2_2") (pintype "unspecified"))
      (node (ref "U5") (pin "2") (pinfunction "VDD3P3_2") (pintype "unspecified"))
      (node (ref "U5") (pin "20") (pinfunction "VDD3P3_RTC_20") (pintype "unspecified"))
      (node (ref "U5") (pin "3") (pinfunction "VDD3P3_3") (pintype "unspecified"))
      (node (ref "U5") (pin "46") (pinfunction "VDD3P3_CPU_46") (pintype "unspecified"))
      (node (ref "U5") (pin "55") (pinfunction "VDDA_55") (pintype "unspecified"))
      (node (ref "U5") (pin "56") (pinfunction "VDDA_56") (pintype "unspecified"))
    )
    (net (code "46") (name "VDD_SPI") (class "Default")
      (node (ref "C13") (pin "2") (pinfunction "2_2") (pintype "unspecified"))
      (node (ref "C14") (pin "2") (pinfunction "2_2") (pintype "input"))
      (node (ref "U4") (pin "8") (pinfunction "VCC_8") (pintype "unspecified"))
      (node (ref "U5") (pin "29") (pinfunction "VDD_SPI_29") (pintype "unspecified"))
    )
    (net (code "47") (name "XTAL_N") (class "Default")
      (node (ref "C18") (pin "1") (pinfunction "1_1") (pintype "input"))
      (node (ref "U5") (pin "53") (pinfunction "XTAL_N_53") (pintype "unspecified"))
      (node (ref "X1") (pin "3") (pinfunction "OSC2_3") (pintype "unspecified"))
    )
    (net (code "48") (name "XTAL_P") (class "Default")
      (node (ref "L2") (pin "1") (pinfunction "1_1") (pintype "unspecified"))
      (node (ref "U5") (pin "54") (pinfunction "XTAL_P_54") (pintype "unspecified"))
    )
    (net (code "49") (name "unconnected-(ANT-Solder{slash}termination-Pad2)") (class "Default")
      (node (ref "ANT") (pin "2") (pinfunction "Solder/termination_2") (pintype "unspecified"))
    )
    (net (code "50") (name "unconnected-(CARSW1-Pad1)") (class "Default")
      (node (ref "CARSW1") (pin "1") (pinfunction "1_1") (pintype "input"))
    )
    (net (code "51") (name "unconnected-(CARSW1-Pad2)") (class "Default")
      (node (ref "CARSW1") (pin "2") (pinfunction "2_2") (pintype "input"))
    )
    (net (code "52") (name "unconnected-(OLED-VBREF-Pad6)") (class "Default")
      (node (ref "OLED") (pin "6") (pinfunction "VBREF_6") (pintype "unspecified+no_connect"))
    )
    (net (code "53") (name "unconnected-(SW1-Pad2)") (class "Default")
      (node (ref "SW1") (pin "2") (pinfunction "2_2") (pintype "unspecified+no_connect"))
    )
    (net (code "54") (name "unconnected-(SW1-Pad4)") (class "Default")
      (node (ref "SW1") (pin "4") (pinfunction "4_4") (pintype "unspecified+no_connect"))
    )
    (net (code "55") (name "unconnected-(SW1-Pad5)") (class "Default")
      (node (ref "SW1") (pin "5") (pinfunction "5_5") (pintype "unspecified+no_connect"))
    )
    (net (code "56") (name "unconnected-(U1-CHRG#-Pad7)") (class "Default")
      (node (ref "U1") (pin "7") (pinfunction "CHRG#_7") (pintype "unspecified+no_connect"))
    )
    (net (code "57") (name "unconnected-(U1-STDBY#-Pad6)") (class "Default")
      (node (ref "U1") (pin "6") (pinfunction "STDBY#_6") (pintype "unspecified+no_connect"))
    )
    (net (code "58") (name "unconnected-(U2-NC-Pad4)") (class "Default")
      (node (ref "U2") (pin "4") (pinfunction "NC_4") (pintype "unspecified+no_connect"))
    )
    (net (code "59") (name "unconnected-(U5-GPIO1-Pad6)") (class "Default")
      (node (ref "U5") (pin "6") (pinfunction "GPIO1_6") (pintype "unspecified+no_connect"))
    )
    (net (code "60") (name "unconnected-(U5-GPIO3-Pad8)") (class "Default")
      (node (ref "U5") (pin "8") (pinfunction "GPIO3_8") (pintype "unspecified+no_connect"))
    )
    (net (code "61") (name "unconnected-(U5-GPIO6-Pad11)") (class "Default")
      (node (ref "U5") (pin "11") (pinfunction "GPIO6_11") (pintype "unspecified+no_connect"))
    )
    (net (code "62") (name "unconnected-(U5-GPIO7-Pad12)") (class "Default")
      (node (ref "U5") (pin "12") (pinfunction "GPIO7_12") (pintype "unspecified+no_connect"))
    )
    (net (code "63") (name "unconnected-(U5-GPIO10-Pad15)") (class "Default")
      (node (ref "U5") (pin "15") (pinfunction "GPIO10_15") (pintype "unspecified+no_connect"))
    )
    (net (code "64") (name "unconnected-(U5-GPIO11-Pad16)") (class "Default")
      (node (ref "U5") (pin "16") (pinfunction "GPIO11_16") (pintype "unspecified+no_connect"))
    )
    (net (code "65") (name "unconnected-(U5-GPIO12-Pad17)") (class "Default")
      (node (ref "U5") (pin "17") (pinfunction "GPIO12_17") (pintype "unspecified+no_connect"))
    )
    (net (code "66") (name "unconnected-(U5-GPIO13-Pad18)") (class "Default")
      (node (ref "U5") (pin "18") (pinfunction "GPIO13_18") (pintype "unspecified+no_connect"))
    )
    (net (code "67") (name "unconnected-(U5-GPIO14-Pad19)") (class "Default")
      (node (ref "U5") (pin "19") (pinfunction "GPIO14_19") (pintype "unspecified+no_connect"))
    )
    (net (code "68") (name "unconnected-(U5-GPIO17-Pad23)") (class "Default")
      (node (ref "U5") (pin "23") (pinfunction "GPIO17_23") (pintype "unspecified+no_connect"))
    )
    (net (code "69") (name "unconnected-(U5-GPIO18-Pad24)") (class "Default")
      (node (ref "U5") (pin "24") (pinfunction "GPIO18_24") (pintype "unspecified+no_connect"))
    )
    (net (code "70") (name "unconnected-(U5-GPIO21-Pad27)") (class "Default")
      (node (ref "U5") (pin "27") (pinfunction "GPIO21_27") (pintype "unspecified+no_connect"))
    )
    (net (code "71") (name "unconnected-(U5-GPIO33-Pad38)") (class "Default")
      (node (ref "U5") (pin "38") (pinfunction "GPIO33_38") (pintype "unspecified+no_connect"))
    )
    (net (code "72") (name "unconnected-(U5-GPIO34-Pad39)") (class "Default")
      (node (ref "U5") (pin "39") (pinfunction "GPIO34_39") (pintype "unspecified+no_connect"))
    )
    (net (code "73") (name "unconnected-(U5-GPIO35-Pad40)") (class "Default")
      (node (ref "U5") (pin "40") (pinfunction "GPIO35_40") (pintype "unspecified+no_connect"))
    )
    (net (code "74") (name "unconnected-(U5-GPIO36-Pad41)") (class "Default")
      (node (ref "U5") (pin "41") (pinfunction "GPIO36_41") (pintype "unspecified+no_connect"))
    )
    (net (code "75") (name "unconnected-(U5-GPIO38-Pad43)") (class "Default")
      (node (ref "U5") (pin "43") (pinfunction "GPIO38_43") (pintype "unspecified+no_connect"))
    )
    (net (code "76") (name "unconnected-(U5-GPIO45-Pad51)") (class "Default")
      (node (ref "U5") (pin "51") (pinfunction "GPIO45_51") (pintype "unspecified+no_connect"))
    )
    (net (code "77") (name "unconnected-(U5-GPIO46-Pad52)") (class "Default")
      (node (ref "U5") (pin "52") (pinfunction "GPIO46_52") (pintype "unspecified+no_connect"))
    )
    (net (code "78") (name "unconnected-(U5-MTCK-Pad44)") (class "Default")
      (node (ref "U5") (pin "44") (pinfunction "MTCK_44") (pintype "unspecified+no_connect"))
    )
    (net (code "79") (name "unconnected-(U5-MTDI-Pad47)") (class "Default")
      (node (ref "U5") (pin "47") (pinfunction "MTDI_47") (pintype "unspecified+no_connect"))
    )
    (net (code "80") (name "unconnected-(U5-MTDO-Pad45)") (class "Default")
      (node (ref "U5") (pin "45") (pinfunction "MTDO_45") (pintype "unspecified+no_connect"))
    )
    (net (code "81") (name "unconnected-(U5-MTMS-Pad48)") (class "Default")
      (node (ref "U5") (pin "48") (pinfunction "MTMS_48") (pintype "unspecified+no_connect"))
    )
    (net (code "82") (name "unconnected-(U5-SPICLK_N-Pad36)") (class "Default")
      (node (ref "U5") (pin "36") (pinfunction "SPICLK_N_36") (pintype "unspecified+no_connect"))
    )
    (net (code "83") (name "unconnected-(U5-SPICLK_P-Pad37)") (class "Default")
      (node (ref "U5") (pin "37") (pinfunction "SPICLK_P_37") (pintype "unspecified+no_connect"))
    )
    (net (code "84") (name "unconnected-(U5-SPICS1-Pad28)") (class "Default")
      (node (ref "U5") (pin "28") (pinfunction "SPICS1_28") (pintype "unspecified+no_connect"))
    )
    (net (code "85") (name "unconnected-(U5-U0RXD-Pad50)") (class "Default")
      (node (ref "U5") (pin "50") (pinfunction "U0RXD_50") (pintype "unspecified+no_connect"))
    )
    (net (code "86") (name "unconnected-(U5-U0TXD-Pad49)") (class "Default")
      (node (ref "U5") (pin "49") (pinfunction "U0TXD_49") (pintype "unspecified+no_connect"))
    )
    (net (code "87") (name "unconnected-(U5-XTAL_32K_N-Pad22)") (class "Default")
      (node (ref "U5") (pin "22") (pinfunction "XTAL_32K_N_22") (pintype "unspecified+no_connect"))
    )
    (net (code "88") (name "unconnected-(U5-XTAL_32K_P-Pad21)") (class "Default")
      (node (ref "U5") (pin "21") (pinfunction "XTAL_32K_P_21") (pintype "unspecified+no_connect"))
    )
    (net (code "89") (name "unconnected-(USBC-SBU1-PadA8)") (class "Default")
      (node (ref "USBC") (pin "A8") (pinfunction "SBU1_A8") (pintype "unspecified+no_connect"))
    )
    (net (code "90") (name "unconnected-(USBC-SBU2-PadB8)") (class "Default")
      (node (ref "USBC") (pin "B8") (pinfunction "SBU2_B8") (pintype "unspecified+no_connect"))
    )
  )
)
